# Motor_TB6612.net
KiCad netlist of a schematic drawn in Altium Designer
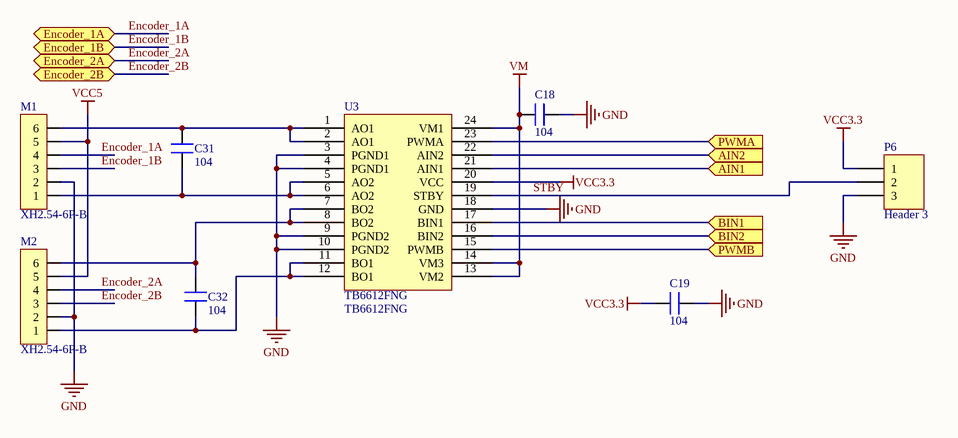
[diagram p0: Motor_TB6612.SchDoc]

(export (version "E")
  (design (tool "Eeschema 10.0.6"))
  (components
    (comp (ref "C18") (value "104") (footprint "0603C") (libsource (lib "WarShip V3 STM32103封装库") (part "C")))
    (comp (ref "C19") (value "104") (footprint "0603C") (libsource (lib "WarShip V3 STM32103封装库") (part "C")))
    (comp (ref "C31") (value "104") (footprint "0603C") (libsource (lib "WarShip V3 STM32103封装库") (part "C")))
    (comp (ref "C32") (value "104") (footprint "0603C") (libsource (lib "WarShip V3 STM32103封装库") (part "C")))
    (comp (ref "M1")
      (value "XH2.54-6P-B")
      (footprint "XH2.54-6P-A")
      (libsource (lib "micro usb") (part "XH2.54-6P-B"))
    )
    (comp (ref "M2")
      (value "XH2.54-6P-B")
      (footprint "XH2.54-6P-A")
      (libsource (lib "micro usb") (part "XH2.54-6P-B"))
    )
    (comp (ref "P6")
      (value "Header 3")
      (footprint "HDR1X3")
      (description "Header, 3-Pin")
      (fields (field (name "PUBLISHER") "Altium Limited"))
      (libsource (lib "Miscellaneous Connectors") (part "Header 3"))
    )
    (comp (ref "U3")
      (value "TB6612FNG")
      (footprint "SSOP24-300-0.65D")
      (libsource (lib "3D库") (part "TB6612FNG"))
    )
  )
  (nets
    (net (code "1") (name "/AIN1") (class "Default")
      (node (ref "U3") (pin "21") (pinfunction "AIN1_21") (pintype "passive"))
    )
    (net (code "2") (name "/AIN2") (class "Default")
      (node (ref "U3") (pin "22") (pinfunction "AIN2_22") (pintype "passive"))
    )
    (net (code "3") (name "/BIN1") (class "Default")
      (node (ref "U3") (pin "17") (pinfunction "BIN1_17") (pintype "passive"))
    )
    (net (code "4") (name "/BIN2") (class "Default")
      (node (ref "U3") (pin "16") (pinfunction "BIN2_16") (pintype "passive"))
    )
    (net (code "5") (name "/Encoder_1A") (class "Default")
      (node (ref "M1") (pin "4") (pinfunction "4_4") (pintype "passive"))
    )
    (net (code "6") (name "/Encoder_1B") (class "Default")
      (node (ref "M1") (pin "3") (pinfunction "3_3") (pintype "passive"))
    )
    (net (code "7") (name "/Encoder_2A") (class "Default")
      (node (ref "M2") (pin "4") (pinfunction "4_4") (pintype "passive"))
    )
    (net (code "8") (name "/Encoder_2B") (class "Default")
      (node (ref "M2") (pin "3") (pinfunction "3_3") (pintype "passive"))
    )
    (net (code "9") (name "/PWMA") (class "Default")
      (node (ref "U3") (pin "23") (pinfunction "PWMA_23") (pintype "passive"))
    )
    (net (code "10") (name "/PWMB") (class "Default")
      (node (ref "U3") (pin "15") (pinfunction "PWMB_15") (pintype "passive"))
    )
    (net (code "11") (name "/STBY") (class "Default")
      (node (ref "P6") (pin "2") (pinfunction "2_2") (pintype "passive"))
      (node (ref "U3") (pin "19") (pinfunction "STBY_19") (pintype "passive"))
    )
    (net (code "12") (name "GND") (class "Default")
      (node (ref "C18") (pin "2") (pintype "passive"))
      (node (ref "C19") (pin "2") (pintype "passive"))
      (node (ref "M1") (pin "2") (pinfunction "2_2") (pintype "passive"))
      (node (ref "M2") (pin "2") (pinfunction "2_2") (pintype "passive"))
      (node (ref "P6") (pin "3") (pinfunction "3_3") (pintype "passive"))
      (node (ref "U3") (pin "10") (pinfunction "PGND2_10") (pintype "passive"))
      (node (ref "U3") (pin "18") (pinfunction "GND_18") (pintype "passive"))
      (node (ref "U3") (pin "3") (pinfunction "PGND1_3") (pintype "passive"))
      (node (ref "U3") (pin "4") (pinfunction "PGND1_4") (pintype "passive"))
      (node (ref "U3") (pin "9") (pinfunction "PGND2_9") (pintype "passive"))
    )
    (net (code "13") (name "Net-(C31-Pad1)") (class "Default")
      (node (ref "C31") (pin "1") (pintype "passive"))
      (node (ref "M1") (pin "1") (pinfunction "1_1") (pintype "passive"))
      (node (ref "U3") (pin "5") (pinfunction "AO2_5") (pintype "passive"))
      (node (ref "U3") (pin "6") (pinfunction "AO2_6") (pintype "passive"))
    )
    (net (code "14") (name "Net-(C31-Pad2)") (class "Default")
      (node (ref "C31") (pin "2") (pintype "passive"))
      (node (ref "M1") (pin "6") (pinfunction "6_6") (pintype "passive"))
      (node (ref "U3") (pin "1") (pinfunction "AO1_1") (pintype "passive"))
      (node (ref "U3") (pin "2") (pinfunction "AO1_2") (pintype "passive"))
    )
    (net (code "15") (name "Net-(C32-Pad1)") (class "Default")
      (node (ref "C32") (pin "1") (pintype "passive"))
      (node (ref "M2") (pin "1") (pinfunction "1_1") (pintype "passive"))
      (node (ref "U3") (pin "11") (pinfunction "BO1_11") (pintype "passive"))
      (node (ref "U3") (pin "12") (pinfunction "BO1_12") (pintype "passive"))
    )
    (net (code "16") (name "Net-(C32-Pad2)") (class "Default")
      (node (ref "C32") (pin "2") (pintype "passive"))
      (node (ref "M2") (pin "6") (pinfunction "6_6") (pintype "passive"))
      (node (ref "U3") (pin "7") (pinfunction "BO2_7") (pintype "passive"))
      (node (ref "U3") (pin "8") (pinfunction "BO2_8") (pintype "passive"))
    )
    (net (code "17") (name "VCC3.3") (class "Default")
      (node (ref "C19") (pin "1") (pintype "passive"))
      (node (ref "P6") (pin "1") (pinfunction "1_1") (pintype "passive"))
      (node (ref "U3") (pin "20") (pinfunction "VCC_20") (pintype "passive"))
    )
    (net (code "18") (name "VCC5") (class "Default")
      (node (ref "M1") (pin "5") (pinfunction "5_5") (pintype "passive"))
      (node (ref "M2") (pin "5") (pinfunction "5_5") (pintype "passive"))
    )
    (net (code "19") (name "VM") (class "Default")
      (node (ref "C18") (pin "1") (pintype "passive"))
      (node (ref "U3") (pin "13") (pinfunction "VM2_13") (pintype "passive"))
      (node (ref "U3") (pin "14") (pinfunction "VM3_14") (pintype "passive"))
      (node (ref "U3") (pin "24") (pinfunction "VM1_24") (pintype "passive"))
    )
  )
)
